# cpu-tiny85.net
KiCad netlist of a schematic drawn in EAGLE
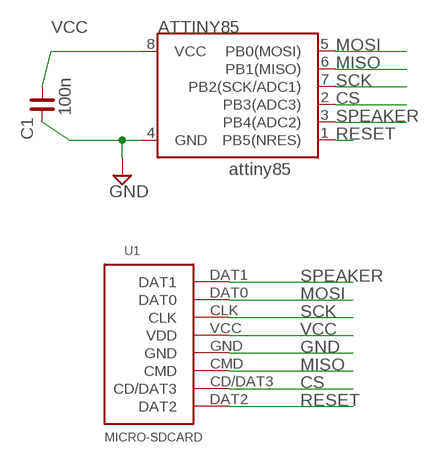
[diagram p0: schematic, sheet 1]

(export (version "E")
  (design (tool "Eeschema 10.0.6"))
  (components
    (comp (ref "ATTINY85")
      (value "ATTINY45")
      (footprint "eagle-import:SO08-EIAJ")
      (libsource (lib "eagle-import") (part "ATTINY45"))
    )
    (comp (ref "C1")
      (value "100n")
      (footprint "eagle-import:C0603")
      (libsource (lib "eagle-import") (part "C_0603"))
    )
    (comp (ref "U1")
      (value "MICRO-SDCARD")
      (footprint "eagle-import:MICRO-SDCARD")
      (libsource (lib "eagle-import") (part "MICRO-SDCARD"))
    )
  )
  (nets
    (net (code "1") (name "/CS") (class "Default")
      (node (ref "ATTINY85") (pin "2") (pinfunction "PB3(ADC3)_2") (pintype "bidirectional"))
      (node (ref "U1") (pin "CD/DAT3") (pinfunction "CD/DAT3_CD/DAT3") (pintype "bidirectional"))
    )
    (net (code "2") (name "/MISO") (class "Default")
      (node (ref "ATTINY85") (pin "6") (pinfunction "PB1(MISO)_6") (pintype "bidirectional"))
      (node (ref "U1") (pin "CMD") (pinfunction "CMD_CMD") (pintype "bidirectional"))
    )
    (net (code "3") (name "/MOSI") (class "Default")
      (node (ref "ATTINY85") (pin "5") (pinfunction "PB0(MOSI)_5") (pintype "bidirectional"))
      (node (ref "U1") (pin "DAT0") (pinfunction "DAT0_DAT0") (pintype "bidirectional"))
    )
    (net (code "4") (name "/RESET") (class "Default")
      (node (ref "ATTINY85") (pin "1") (pinfunction "PB5(NRES)_1") (pintype "bidirectional"))
      (node (ref "U1") (pin "DAT2") (pinfunction "DAT2_DAT2") (pintype "bidirectional"))
    )
    (net (code "5") (name "/SCK") (class "Default")
      (node (ref "ATTINY85") (pin "7") (pinfunction "PB2(SCK/ADC1)_7") (pintype "bidirectional"))
      (node (ref "U1") (pin "CLK") (pinfunction "CLK_CLK") (pintype "bidirectional"))
    )
    (net (code "6") (name "/SPEAKER") (class "Default")
      (node (ref "ATTINY85") (pin "3") (pinfunction "PB4(ADC2)_3") (pintype "bidirectional"))
      (node (ref "U1") (pin "DAT1") (pinfunction "DAT1_DAT1") (pintype "bidirectional"))
    )
    (net (code "7") (name "/VCC") (class "Default")
      (node (ref "ATTINY85") (pin "8") (pinfunction "VCC_8") (pintype "bidirectional"))
      (node (ref "C1") (pin "1") (pinfunction "1_1") (pintype "passive"))
      (node (ref "U1") (pin "VCC") (pinfunction "VDD_VCC") (pintype "bidirectional"))
    )
    (net (code "8") (name "GND") (class "Default")
      (node (ref "ATTINY85") (pin "4") (pinfunction "GND_4") (pintype "bidirectional"))
      (node (ref "C1") (pin "2") (pinfunction "2_2") (pintype "passive"))
      (node (ref "U1") (pin "GND") (pinfunction "GND_GND") (pintype "bidirectional"))
    )
  )
)
